# 05_Buzzer.net
KiCad netlist of a schematic drawn in Altium Designer
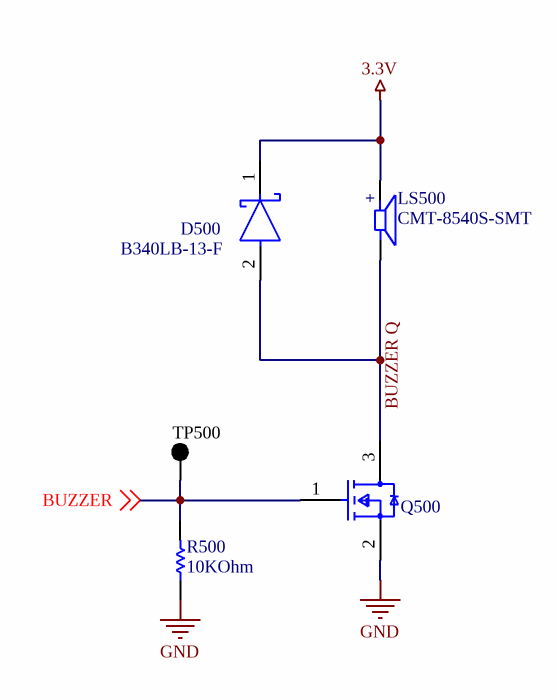
[diagram p0: 05_Buzzer.SchDoc]

(export (version "E")
  (design (tool "Eeschema 10.0.6"))
  (components
    (comp (ref "D500")
      (value "B340LB-13-F")
      (footprint "FP-SMB-MFG")
      (description "DIODE SCHOTTKY 40V 3A SMB")
      (fields
        (field (name "OCTOPART") "https://octopart.com/b340lb-13-f-diodes+inc.-325823")
        (field (name "MANUFACTURER") "Diodes Inc.")
      )
      (libsource (lib "Altium Content Vault") (part "1d6ec82d83fb6aee721767c19dac4b9"))
    )
    (comp (ref "LS500")
      (value "CMT-8540S-SMT")
      (footprint "MBT_Footprint")
      (description "8.5 mm, 5.0 Vo-p, 100 dB, Surface Mount (SMT), Magnetic Audio Transducer Buzzer")
      (fields
        (field (name "MF") "CUI Devices")
        (field (name "MP") "CMT-8540S-SMT-TR")
        (field (name "DRAWN BY") "Adam Shebani")
      )
      (libsource (lib "ECE315-F25") (part "CMT-8540S-SMT"))
    )
    (comp (ref "Q500")
      (value "2N7002-7-F")
      (footprint "FP-SOT23-MFG")
      (description "MOSFET N-CH 60V 115MA SOT23-3")
      (fields (field (name "VOLTAGE") "60V"))
      (libsource (lib "Altium Content Vault") (part "3b9c635fedb024a5347a57b145af9cc"))
    )
    (comp (ref "R500")
      (value "RC1206FR-0710KL")
      (footprint "RESC3116X65X40ML10T20")
      (description "Chip Resistor, 10 KOhm, +/- 1%, 0.25 W, -55 to 155 degC, 1206 (3216 Metric), RoHS, Tape and Reel")
      (fields
        (field (name "TOLERANCE") "1%")
        (field (name "RESISTANCE") "10KOhm")
        (field (name "MANUFACTURER") "Yageo")
      )
      (libsource (lib "Altium Content Vault") (part "RES-2"))
    )
    (comp (ref "TP500")
      (value "5011")
      (footprint "KSTN-5011_V")
      (description "Test Point, Black, Through Hole, RoHS, Bulk")
      (fields (field (name "MANUFACTURER") "Keystone"))
      (libsource (lib "Altium Content Vault") (part "TESTPOINT_BLACK"))
    )
  )
  (nets
    (net (code "1") (name "/BUZZER Q") (class "Default")
      (node (ref "D500") (pin "2") (pinfunction "A_2") (pintype "passive"))
      (node (ref "LS500") (pin "N") (pinfunction "N_N") (pintype "passive"))
      (node (ref "Q500") (pin "3") (pinfunction "D_3") (pintype "passive"))
    )
    (net (code "2") (name "3.3V") (class "Default")
      (node (ref "D500") (pin "1") (pinfunction "C_1") (pintype "passive"))
      (node (ref "LS500") (pin "P") (pinfunction "P_P") (pintype "passive"))
    )
    (net (code "3") (name "BUZZER") (class "Default")
      (node (ref "Q500") (pin "1") (pinfunction "G_1") (pintype "passive"))
      (node (ref "R500") (pin "2") (pinfunction "2_2") (pintype "passive"))
      (node (ref "TP500") (pin "1") (pinfunction "1_1") (pintype "passive"))
    )
    (net (code "4") (name "GND") (class "Default")
      (node (ref "Q500") (pin "2") (pinfunction "S_2") (pintype "passive"))
      (node (ref "R500") (pin "1") (pinfunction "1_1") (pintype "passive"))
    )
  )
)
